# Div.net
KiCad netlist of a schematic drawn in EAGLE
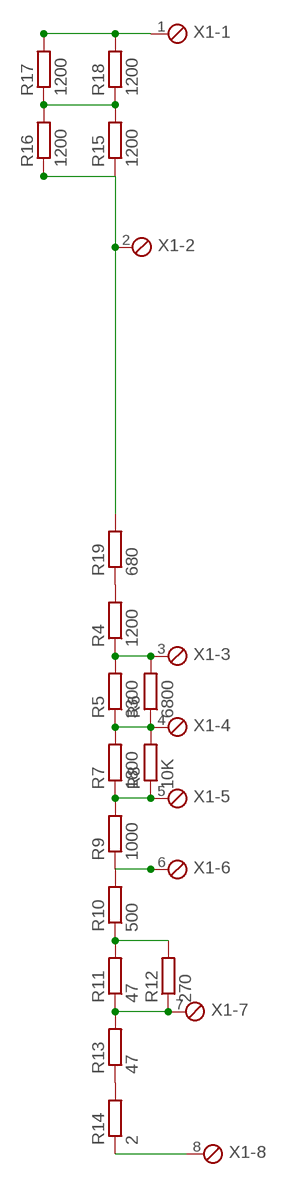
[diagram p0: schematic, sheet 1]

(export (version "E")
  (design (tool "Eeschema 10.0.6"))
  (components
    (comp (ref "R4")
      (value "1200")
      (footprint "eagle-import:0309_12")
      (libsource (lib "eagle-import") (part "R-EU_0309/12"))
    )
    (comp (ref "R5")
      (value "3300")
      (footprint "eagle-import:0309_10")
      (libsource (lib "eagle-import") (part "R-EU_0309/10"))
    )
    (comp (ref "R6")
      (value "6800")
      (footprint "eagle-import:0309_10")
      (libsource (lib "eagle-import") (part "R-EU_0309/10"))
    )
    (comp (ref "R7")
      (value "1800")
      (footprint "eagle-import:0309_10")
      (libsource (lib "eagle-import") (part "R-EU_0309/10"))
    )
    (comp (ref "R8")
      (value "10K")
      (footprint "eagle-import:0309_10")
      (libsource (lib "eagle-import") (part "R-EU_0309/10"))
    )
    (comp (ref "R9")
      (value "1000")
      (footprint "eagle-import:0309_10")
      (libsource (lib "eagle-import") (part "R-EU_0309/10"))
    )
    (comp (ref "R10")
      (value "500")
      (footprint "eagle-import:0309_10")
      (libsource (lib "eagle-import") (part "R-EU_0309/10"))
    )
    (comp (ref "R11")
      (value "47")
      (footprint "eagle-import:0309_10")
      (libsource (lib "eagle-import") (part "R-EU_0309/10"))
    )
    (comp (ref "R12")
      (value "270")
      (footprint "eagle-import:0309_10")
      (libsource (lib "eagle-import") (part "R-EU_0309/10"))
    )
    (comp (ref "R13")
      (value "47")
      (footprint "eagle-import:0309_10")
      (libsource (lib "eagle-import") (part "R-EU_0309/10"))
    )
    (comp (ref "R14")
      (value "2")
      (footprint "eagle-import:0309_10")
      (libsource (lib "eagle-import") (part "R-EU_0309/10"))
    )
    (comp (ref "R15")
      (value "1200")
      (footprint "eagle-import:0309_12")
      (libsource (lib "eagle-import") (part "R-EU_0309/12"))
    )
    (comp (ref "R16")
      (value "1200")
      (footprint "eagle-import:0309_12")
      (libsource (lib "eagle-import") (part "R-EU_0309/12"))
    )
    (comp (ref "R17")
      (value "1200")
      (footprint "eagle-import:0309_12")
      (libsource (lib "eagle-import") (part "R-EU_0309/12"))
    )
    (comp (ref "R18")
      (value "1200")
      (footprint "eagle-import:0309_12")
      (libsource (lib "eagle-import") (part "R-EU_0309/12"))
    )
    (comp (ref "R19")
      (value "680")
      (footprint "eagle-import:0309_10")
      (libsource (lib "eagle-import") (part "R-EU_0309/10"))
    )
    (comp (ref "X1")
      (value "MPT8")
      (footprint "eagle-import:8POL254")
      (libsource (lib "eagle-import") (part "MPT8"))
    )
  )
  (nets
    (net (code "1") (name "Net-(R10-Pad1)") (class "Default")
      (node (ref "R10") (pin "1") (pinfunction "1_1") (pintype "passive"))
      (node (ref "R11") (pin "2") (pinfunction "2_2") (pintype "passive"))
      (node (ref "R12") (pin "2") (pinfunction "2_2") (pintype "passive"))
    )
    (net (code "2") (name "Net-(R13-Pad1)") (class "Default")
      (node (ref "R13") (pin "1") (pinfunction "1_1") (pintype "passive"))
      (node (ref "R14") (pin "2") (pinfunction "2_2") (pintype "passive"))
    )
    (net (code "3") (name "Net-(R15-Pad2)") (class "Default")
      (node (ref "R15") (pin "2") (pinfunction "2_2") (pintype "passive"))
      (node (ref "R16") (pin "2") (pinfunction "2_2") (pintype "passive"))
      (node (ref "R17") (pin "1") (pinfunction "1_1") (pintype "passive"))
      (node (ref "R18") (pin "1") (pinfunction "1_1") (pintype "passive"))
    )
    (net (code "4") (name "Net-(R17-Pad2)") (class "Default")
      (node (ref "R17") (pin "2") (pinfunction "2_2") (pintype "passive"))
      (node (ref "R18") (pin "2") (pinfunction "2_2") (pintype "passive"))
      (node (ref "X1") (pin "1") (pinfunction "1_1") (pintype "passive"))
    )
    (net (code "5") (name "Net-(R19-Pad1)") (class "Default")
      (node (ref "R19") (pin "1") (pinfunction "1_1") (pintype "passive"))
      (node (ref "R4") (pin "2") (pinfunction "2_2") (pintype "passive"))
    )
    (net (code "6") (name "Net-(X1B-1)") (class "Default")
      (node (ref "R15") (pin "1") (pinfunction "1_1") (pintype "passive"))
      (node (ref "R16") (pin "1") (pinfunction "1_1") (pintype "passive"))
      (node (ref "R19") (pin "2") (pinfunction "2_2") (pintype "passive"))
      (node (ref "X1") (pin "2") (pinfunction "1_2") (pintype "passive"))
    )
    (net (code "7") (name "Net-(X1C-1)") (class "Default")
      (node (ref "R4") (pin "1") (pinfunction "1_1") (pintype "passive"))
      (node (ref "R5") (pin "2") (pinfunction "2_2") (pintype "passive"))
      (node (ref "R6") (pin "2") (pinfunction "2_2") (pintype "passive"))
      (node (ref "X1") (pin "3") (pinfunction "1_3") (pintype "passive"))
    )
    (net (code "8") (name "Net-(X1D-1)") (class "Default")
      (node (ref "R5") (pin "1") (pinfunction "1_1") (pintype "passive"))
      (node (ref "R6") (pin "1") (pinfunction "1_1") (pintype "passive"))
      (node (ref "R7") (pin "2") (pinfunction "2_2") (pintype "passive"))
      (node (ref "R8") (pin "2") (pinfunction "2_2") (pintype "passive"))
      (node (ref "X1") (pin "4") (pinfunction "1_4") (pintype "passive"))
    )
    (net (code "9") (name "Net-(X1E-1)") (class "Default")
      (node (ref "R7") (pin "1") (pinfunction "1_1") (pintype "passive"))
      (node (ref "R8") (pin "1") (pinfunction "1_1") (pintype "passive"))
      (node (ref "R9") (pin "2") (pinfunction "2_2") (pintype "passive"))
      (node (ref "X1") (pin "5") (pinfunction "1_5") (pintype "passive"))
    )
    (net (code "10") (name "Net-(X1F-1)") (class "Default")
      (node (ref "R10") (pin "2") (pinfunction "2_2") (pintype "passive"))
      (node (ref "R9") (pin "1") (pinfunction "1_1") (pintype "passive"))
      (node (ref "X1") (pin "6") (pinfunction "1_6") (pintype "passive"))
    )
    (net (code "11") (name "Net-(X1G-1)") (class "Default")
      (node (ref "R11") (pin "1") (pinfunction "1_1") (pintype "passive"))
      (node (ref "R12") (pin "1") (pinfunction "1_1") (pintype "passive"))
      (node (ref "R13") (pin "2") (pinfunction "2_2") (pintype "passive"))
      (node (ref "X1") (pin "7") (pinfunction "1_7") (pintype "passive"))
    )
    (net (code "12") (name "Net-(X1H-1)") (class "Default")
      (node (ref "R14") (pin "1") (pinfunction "1_1") (pintype "passive"))
      (node (ref "X1") (pin "8") (pinfunction "1_8") (pintype "passive"))
    )
  )
)
